# GroupeK.net
KiCad netlist of a schematic drawn in EAGLE
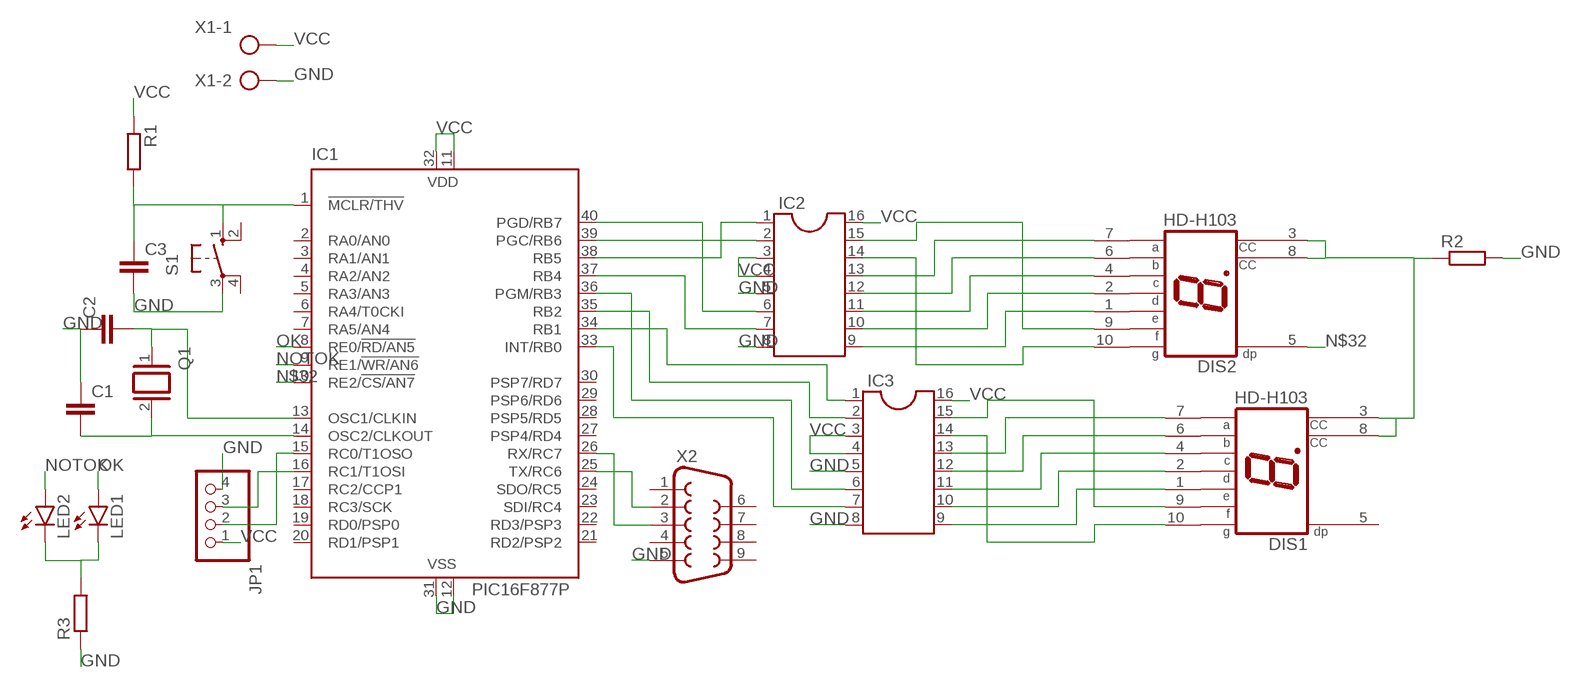
[diagram p0: schematic, sheet 1]

(export (version "E")
  (design (tool "Eeschema 10.0.6"))
  (components
    (comp (ref "C1")
      (value "C-EU025-025X050")
      (footprint "eagle-import:C025-025X050")
      (libsource (lib "eagle-import") (part "C-EU025-025X050"))
    )
    (comp (ref "C2")
      (value "C-EU025-025X050")
      (footprint "eagle-import:C025-025X050")
      (libsource (lib "eagle-import") (part "C-EU025-025X050"))
    )
    (comp (ref "C3")
      (value "C-EU025-025X050")
      (footprint "eagle-import:C025-025X050")
      (libsource (lib "eagle-import") (part "C-EU025-025X050"))
    )
    (comp (ref "DIS1")
      (value "HD-H103")
      (footprint "eagle-import:HDSP-M")
      (libsource (lib "eagle-import") (part "HD-H103"))
    )
    (comp (ref "DIS2")
      (value "HD-H103")
      (footprint "eagle-import:HDSP-M")
      (libsource (lib "eagle-import") (part "HD-H103"))
    )
    (comp (ref "IC1")
      (value "PIC16F877P")
      (footprint "eagle-import:DIL40")
      (fields (field (name "MF") "MICROCHIP") (field (name "MPN") "PIC16F877-04/P"))
      (libsource (lib "eagle-import") (part "PIC16F87P7"))
    )
    (comp (ref "IC2")
      (value "DIL16")
      (footprint "eagle-import:DIL16")
      (libsource (lib "eagle-import") (part "DIL16"))
    )
    (comp (ref "IC3")
      (value "DIL16")
      (footprint "eagle-import:DIL16")
      (libsource (lib "eagle-import") (part "DIL16"))
    )
    (comp (ref "JP1")
      (value "PINHD-1X4")
      (footprint "eagle-import:1X04")
      (libsource (lib "eagle-import") (part "PINHD-1X4"))
    )
    (comp (ref "LED1")
      (value "LED5MM")
      (footprint "eagle-import:LED5MM")
      (libsource (lib "eagle-import") (part "LED5MM"))
    )
    (comp (ref "LED2")
      (value "LED5MM")
      (footprint "eagle-import:LED5MM")
      (libsource (lib "eagle-import") (part "LED5MM"))
    )
    (comp (ref "Q1")
      (value "XTAL/S")
      (footprint "eagle-import:QS")
      (libsource (lib "eagle-import") (part "XTAL/S"))
    )
    (comp (ref "R1")
      (value "R-EU_0207/10")
      (footprint "eagle-import:0207_10")
      (libsource (lib "eagle-import") (part "R-EU_0207/10"))
    )
    (comp (ref "R2")
      (value "R-EU_0207/10")
      (footprint "eagle-import:0207_10")
      (libsource (lib "eagle-import") (part "R-EU_0207/10"))
    )
    (comp (ref "R3")
      (value "R-EU_0207/10")
      (footprint "eagle-import:0207_10")
      (libsource (lib "eagle-import") (part "R-EU_0207/10"))
    )
    (comp (ref "S1")
      (value "10-XX")
      (footprint "eagle-import:B3F-10XX")
      (fields (field (name "MPN") "B3F-1000"))
      (libsource (lib "eagle-import") (part "10-XX"))
    )
    (comp (ref "X1")
      (value "AK300/2")
      (footprint "eagle-import:AK300_2")
      (libsource (lib "eagle-import") (part "AK300/2"))
    )
    (comp (ref "X2")
      (value "F09H")
      (footprint "eagle-import:F09H")
      (libsource (lib "eagle-import") (part "F09H"))
    )
  )
  (nets
    (net (code "1") (name "/GND") (class "Default")
      (node (ref "C1") (pin "1") (pinfunction "1_1") (pintype "passive"))
      (node (ref "C2") (pin "1") (pinfunction "1_1") (pintype "passive"))
      (node (ref "C3") (pin "2") (pinfunction "2_2") (pintype "passive"))
      (node (ref "IC1") (pin "12") (pinfunction "VSS_12") (pintype "power_in"))
      (node (ref "IC1") (pin "31") (pinfunction "VSS_31") (pintype "power_in"))
      (node (ref "IC2") (pin "5") (pinfunction "5_5") (pintype "passive"))
      (node (ref "IC2") (pin "8") (pinfunction "8_8") (pintype "passive"))
      (node (ref "IC3") (pin "5") (pinfunction "5_5") (pintype "passive"))
      (node (ref "IC3") (pin "8") (pinfunction "8_8") (pintype "passive"))
      (node (ref "JP1") (pin "4") (pinfunction "4_4") (pintype "passive"))
      (node (ref "R2") (pin "2") (pinfunction "2_2") (pintype "passive"))
      (node (ref "R3") (pin "1") (pinfunction "1_1") (pintype "passive"))
      (node (ref "S1") (pin "3") (pinfunction "P_3") (pintype "passive"))
      (node (ref "X1") (pin "2") (pinfunction "KL_2") (pintype "passive"))
      (node (ref "X2") (pin "5") (pinfunction "5_5") (pintype "passive"))
    )
    (net (code "2") (name "/N$32") (class "Default")
      (node (ref "DIS2") (pin "5") (pinfunction "DP_5") (pintype "passive"))
      (node (ref "IC1") (pin "10") (pinfunction "RE2/~{CS/AN7}_10") (pintype "bidirectional"))
    )
    (net (code "3") (name "/NOTOK") (class "Default")
      (node (ref "IC1") (pin "9") (pinfunction "RE1/~{WR/AN6}_9") (pintype "bidirectional"))
      (node (ref "LED2") (pin "A") (pinfunction "A_A") (pintype "passive"))
    )
    (net (code "4") (name "/OK") (class "Default")
      (node (ref "IC1") (pin "8") (pinfunction "RE0/~{RD/AN5}_8") (pintype "bidirectional"))
      (node (ref "LED1") (pin "A") (pinfunction "A_A") (pintype "passive"))
    )
    (net (code "5") (name "/VCC") (class "Default")
      (node (ref "IC1") (pin "11") (pinfunction "VDD_11") (pintype "power_in"))
      (node (ref "IC1") (pin "32") (pinfunction "VDD_32") (pintype "power_in"))
      (node (ref "IC2") (pin "16") (pinfunction "16_16") (pintype "passive"))
      (node (ref "IC2") (pin "3") (pinfunction "3_3") (pintype "passive"))
      (node (ref "IC2") (pin "4") (pinfunction "4_4") (pintype "passive"))
      (node (ref "IC3") (pin "16") (pinfunction "16_16") (pintype "passive"))
      (node (ref "IC3") (pin "3") (pinfunction "3_3") (pintype "passive"))
      (node (ref "IC3") (pin "4") (pinfunction "4_4") (pintype "passive"))
      (node (ref "JP1") (pin "1") (pinfunction "1_1") (pintype "passive"))
      (node (ref "R1") (pin "1") (pinfunction "1_1") (pintype "passive"))
      (node (ref "X1") (pin "1") (pinfunction "KL_1") (pintype "passive"))
    )
    (net (code "6") (name "Net-(DIS1-A)") (class "Default")
      (node (ref "DIS1") (pin "7") (pinfunction "A_7") (pintype "passive"))
      (node (ref "IC3") (pin "13") (pinfunction "13_13") (pintype "passive"))
    )
    (net (code "7") (name "Net-(DIS1-B)") (class "Default")
      (node (ref "DIS1") (pin "6") (pinfunction "B_6") (pintype "passive"))
      (node (ref "IC3") (pin "12") (pinfunction "12_12") (pintype "passive"))
    )
    (net (code "8") (name "Net-(DIS1-C)") (class "Default")
      (node (ref "DIS1") (pin "4") (pinfunction "C_4") (pintype "passive"))
      (node (ref "IC3") (pin "11") (pinfunction "11_11") (pintype "passive"))
    )
    (net (code "9") (name "Net-(DIS1-CC-Pad3)") (class "Default")
      (node (ref "DIS1") (pin "3") (pinfunction "CC_3") (pintype "passive"))
      (node (ref "DIS1") (pin "8") (pinfunction "CC_8") (pintype "passive"))
      (node (ref "DIS2") (pin "3") (pinfunction "CC_3") (pintype "passive"))
      (node (ref "DIS2") (pin "8") (pinfunction "CC_8") (pintype "passive"))
      (node (ref "R2") (pin "1") (pinfunction "1_1") (pintype "passive"))
    )
    (net (code "10") (name "Net-(DIS1-D)") (class "Default")
      (node (ref "DIS1") (pin "2") (pinfunction "D_2") (pintype "passive"))
      (node (ref "IC3") (pin "10") (pinfunction "10_10") (pintype "passive"))
    )
    (net (code "11") (name "Net-(DIS1-E)") (class "Default")
      (node (ref "DIS1") (pin "1") (pinfunction "E_1") (pintype "passive"))
      (node (ref "IC3") (pin "9") (pinfunction "9_9") (pintype "passive"))
    )
    (net (code "12") (name "Net-(DIS1-F)") (class "Default")
      (node (ref "DIS1") (pin "9") (pinfunction "F_9") (pintype "passive"))
      (node (ref "IC3") (pin "15") (pinfunction "15_15") (pintype "passive"))
    )
    (net (code "13") (name "Net-(DIS1-G)") (class "Default")
      (node (ref "DIS1") (pin "10") (pinfunction "G_10") (pintype "passive"))
      (node (ref "IC3") (pin "14") (pinfunction "14_14") (pintype "passive"))
    )
    (net (code "14") (name "Net-(DIS2-A)") (class "Default")
      (node (ref "DIS2") (pin "7") (pinfunction "A_7") (pintype "passive"))
      (node (ref "IC2") (pin "13") (pinfunction "13_13") (pintype "passive"))
    )
    (net (code "15") (name "Net-(DIS2-B)") (class "Default")
      (node (ref "DIS2") (pin "6") (pinfunction "B_6") (pintype "passive"))
      (node (ref "IC2") (pin "12") (pinfunction "12_12") (pintype "passive"))
    )
    (net (code "16") (name "Net-(DIS2-C)") (class "Default")
      (node (ref "DIS2") (pin "4") (pinfunction "C_4") (pintype "passive"))
      (node (ref "IC2") (pin "11") (pinfunction "11_11") (pintype "passive"))
    )
    (net (code "17") (name "Net-(DIS2-D)") (class "Default")
      (node (ref "DIS2") (pin "2") (pinfunction "D_2") (pintype "passive"))
      (node (ref "IC2") (pin "10") (pinfunction "10_10") (pintype "passive"))
    )
    (net (code "18") (name "Net-(DIS2-E)") (class "Default")
      (node (ref "DIS2") (pin "1") (pinfunction "E_1") (pintype "passive"))
      (node (ref "IC2") (pin "9") (pinfunction "9_9") (pintype "passive"))
    )
    (net (code "19") (name "Net-(DIS2-F)") (class "Default")
      (node (ref "DIS2") (pin "9") (pinfunction "F_9") (pintype "passive"))
      (node (ref "IC2") (pin "15") (pinfunction "15_15") (pintype "passive"))
    )
    (net (code "20") (name "Net-(DIS2-G)") (class "Default")
      (node (ref "DIS2") (pin "10") (pinfunction "G_10") (pintype "passive"))
      (node (ref "IC2") (pin "14") (pinfunction "14_14") (pintype "passive"))
    )
    (net (code "21") (name "Net-(IC1-INT{slash}RB0)") (class "Default")
      (node (ref "IC1") (pin "33") (pinfunction "INT/RB0_33") (pintype "bidirectional"))
      (node (ref "IC3") (pin "7") (pinfunction "7_7") (pintype "passive"))
    )
    (net (code "22") (name "Net-(IC1-OSC1{slash}CLKIN)") (class "Default")
      (node (ref "C2") (pin "2") (pinfunction "2_2") (pintype "passive"))
      (node (ref "IC1") (pin "13") (pinfunction "OSC1/CLKIN_13") (pintype "input"))
      (node (ref "Q1") (pin "1") (pinfunction "1_1") (pintype "passive"))
    )
    (net (code "23") (name "Net-(IC1-OSC2{slash}CLKOUT)") (class "Default")
      (node (ref "C1") (pin "2") (pinfunction "2_2") (pintype "passive"))
      (node (ref "IC1") (pin "14") (pinfunction "OSC2/CLKOUT_14") (pintype "output"))
      (node (ref "Q1") (pin "2") (pinfunction "2_2") (pintype "passive"))
    )
    (net (code "24") (name "Net-(IC1-PGC{slash}RB6)") (class "Default")
      (node (ref "IC1") (pin "39") (pinfunction "PGC/RB6_39") (pintype "bidirectional"))
      (node (ref "IC2") (pin "2") (pinfunction "2_2") (pintype "passive"))
    )
    (net (code "25") (name "Net-(IC1-PGD{slash}RB7)") (class "Default")
      (node (ref "IC1") (pin "40") (pinfunction "PGD/RB7_40") (pintype "bidirectional"))
      (node (ref "IC2") (pin "6") (pinfunction "6_6") (pintype "passive"))
    )
    (net (code "26") (name "Net-(IC1-PGM{slash}RB3)") (class "Default")
      (node (ref "IC1") (pin "36") (pinfunction "PGM/RB3_36") (pintype "bidirectional"))
      (node (ref "IC3") (pin "6") (pinfunction "6_6") (pintype "passive"))
    )
    (net (code "27") (name "Net-(IC1-RB1)") (class "Default")
      (node (ref "IC1") (pin "34") (pinfunction "RB1_34") (pintype "bidirectional"))
      (node (ref "IC3") (pin "1") (pinfunction "1_1") (pintype "passive"))
    )
    (net (code "28") (name "Net-(IC1-RB2)") (class "Default")
      (node (ref "IC1") (pin "35") (pinfunction "RB2_35") (pintype "bidirectional"))
      (node (ref "IC3") (pin "2") (pinfunction "2_2") (pintype "passive"))
    )
    (net (code "29") (name "Net-(IC1-RB4)") (class "Default")
      (node (ref "IC1") (pin "37") (pinfunction "RB4_37") (pintype "bidirectional"))
      (node (ref "IC2") (pin "7") (pinfunction "7_7") (pintype "passive"))
    )
    (net (code "30") (name "Net-(IC1-RB5)") (class "Default")
      (node (ref "IC1") (pin "38") (pinfunction "RB5_38") (pintype "bidirectional"))
      (node (ref "IC2") (pin "1") (pinfunction "1_1") (pintype "passive"))
    )
    (net (code "31") (name "Net-(IC1-RC0{slash}T1OSO)") (class "Default")
      (node (ref "IC1") (pin "15") (pinfunction "RC0/T1OSO_15") (pintype "bidirectional"))
      (node (ref "JP1") (pin "2") (pinfunction "2_2") (pintype "passive"))
    )
    (net (code "32") (name "Net-(IC1-RC1{slash}T1OSI)") (class "Default")
      (node (ref "IC1") (pin "16") (pinfunction "RC1/T1OSI_16") (pintype "bidirectional"))
      (node (ref "JP1") (pin "3") (pinfunction "3_3") (pintype "passive"))
    )
    (net (code "33") (name "Net-(IC1-RX{slash}RC7)") (class "Default")
      (node (ref "IC1") (pin "26") (pinfunction "RX/RC7_26") (pintype "bidirectional"))
      (node (ref "X2") (pin "3") (pinfunction "3_3") (pintype "passive"))
    )
    (net (code "34") (name "Net-(IC1-TX{slash}RC6)") (class "Default")
      (node (ref "IC1") (pin "25") (pinfunction "TX/RC6_25") (pintype "bidirectional"))
      (node (ref "X2") (pin "2") (pinfunction "2_2") (pintype "passive"))
    )
    (net (code "35") (name "Net-(IC1-~{MCLR{slash}THV})") (class "Default")
      (node (ref "C3") (pin "1") (pinfunction "1_1") (pintype "passive"))
      (node (ref "IC1") (pin "1") (pinfunction "~{MCLR/THV}_1") (pintype "input"))
      (node (ref "R1") (pin "2") (pinfunction "2_2") (pintype "passive"))
      (node (ref "S1") (pin "1") (pinfunction "S_1") (pintype "passive"))
    )
    (net (code "36") (name "Net-(LED1-C)") (class "Default")
      (node (ref "LED1") (pin "K") (pinfunction "C_K") (pintype "passive"))
      (node (ref "LED2") (pin "K") (pinfunction "C_K") (pintype "passive"))
      (node (ref "R3") (pin "2") (pinfunction "2_2") (pintype "passive"))
    )
    (net (code "37") (name "unconnected-(DIS1-DP-Pad5)") (class "Default")
      (node (ref "DIS1") (pin "5") (pinfunction "DP_5") (pintype "passive"))
    )
    (net (code "38") (name "unconnected-(IC1-PSP4{slash}RD4-Pad27)") (class "Default")
      (node (ref "IC1") (pin "27") (pinfunction "PSP4/RD4_27") (pintype "bidirectional"))
    )
    (net (code "39") (name "unconnected-(IC1-PSP5{slash}RD5-Pad28)") (class "Default")
      (node (ref "IC1") (pin "28") (pinfunction "PSP5/RD5_28") (pintype "bidirectional"))
    )
    (net (code "40") (name "unconnected-(IC1-PSP6{slash}RD6-Pad29)") (class "Default")
      (node (ref "IC1") (pin "29") (pinfunction "PSP6/RD6_29") (pintype "bidirectional"))
    )
    (net (code "41") (name "unconnected-(IC1-PSP7{slash}RD7-Pad30)") (class "Default")
      (node (ref "IC1") (pin "30") (pinfunction "PSP7/RD7_30") (pintype "bidirectional"))
    )
    (net (code "42") (name "unconnected-(IC1-RA0{slash}AN0-Pad2)") (class "Default")
      (node (ref "IC1") (pin "2") (pinfunction "RA0/AN0_2") (pintype "bidirectional"))
    )
    (net (code "43") (name "unconnected-(IC1-RA1{slash}AN1-Pad3)") (class "Default")
      (node (ref "IC1") (pin "3") (pinfunction "RA1/AN1_3") (pintype "bidirectional"))
    )
    (net (code "44") (name "unconnected-(IC1-RA2{slash}AN2-Pad4)") (class "Default")
      (node (ref "IC1") (pin "4") (pinfunction "RA2/AN2_4") (pintype "bidirectional"))
    )
    (net (code "45") (name "unconnected-(IC1-RA3{slash}AN3-Pad5)") (class "Default")
      (node (ref "IC1") (pin "5") (pinfunction "RA3/AN3_5") (pintype "bidirectional"))
    )
    (net (code "46") (name "unconnected-(IC1-RA4{slash}T0CKI-Pad6)") (class "Default")
      (node (ref "IC1") (pin "6") (pinfunction "RA4/T0CKI_6") (pintype "bidirectional"))
    )
    (net (code "47") (name "unconnected-(IC1-RA5{slash}AN4-Pad7)") (class "Default")
      (node (ref "IC1") (pin "7") (pinfunction "RA5/AN4_7") (pintype "bidirectional"))
    )
    (net (code "48") (name "unconnected-(IC1-RC2{slash}CCP1-Pad17)") (class "Default")
      (node (ref "IC1") (pin "17") (pinfunction "RC2/CCP1_17") (pintype "bidirectional"))
    )
    (net (code "49") (name "unconnected-(IC1-RC3{slash}SCK-Pad18)") (class "Default")
      (node (ref "IC1") (pin "18") (pinfunction "RC3/SCK_18") (pintype "bidirectional"))
    )
    (net (code "50") (name "unconnected-(IC1-RD0{slash}PSP0-Pad19)") (class "Default")
      (node (ref "IC1") (pin "19") (pinfunction "RD0/PSP0_19") (pintype "bidirectional"))
    )
    (net (code "51") (name "unconnected-(IC1-RD1{slash}PSP1-Pad20)") (class "Default")
      (node (ref "IC1") (pin "20") (pinfunction "RD1/PSP1_20") (pintype "bidirectional"))
    )
    (net (code "52") (name "unconnected-(IC1-RD2{slash}PSP2-Pad21)") (class "Default")
      (node (ref "IC1") (pin "21") (pinfunction "RD2/PSP2_21") (pintype "bidirectional"))
    )
    (net (code "53") (name "unconnected-(IC1-RD3{slash}PSP3-Pad22)") (class "Default")
      (node (ref "IC1") (pin "22") (pinfunction "RD3/PSP3_22") (pintype "bidirectional"))
    )
    (net (code "54") (name "unconnected-(IC1-SDI{slash}RC4-Pad23)") (class "Default")
      (node (ref "IC1") (pin "23") (pinfunction "SDI/RC4_23") (pintype "bidirectional"))
    )
    (net (code "55") (name "unconnected-(IC1-SDO{slash}RC5-Pad24)") (class "Default")
      (node (ref "IC1") (pin "24") (pinfunction "SDO/RC5_24") (pintype "bidirectional"))
    )
    (net (code "56") (name "unconnected-(S1-P1-Pad4)") (class "Default")
      (node (ref "S1") (pin "4") (pinfunction "P1_4") (pintype "passive"))
    )
    (net (code "57") (name "unconnected-(S1-S1-Pad2)") (class "Default")
      (node (ref "S1") (pin "2") (pinfunction "S1_2") (pintype "passive"))
    )
    (net (code "58") (name "unconnected-(X2-Pad1)") (class "Default")
      (node (ref "X2") (pin "1") (pinfunction "1_1") (pintype "passive"))
    )
    (net (code "59") (name "unconnected-(X2-Pad4)") (class "Default")
      (node (ref "X2") (pin "4") (pinfunction "4_4") (pintype "passive"))
    )
    (net (code "60") (name "unconnected-(X2-Pad6)") (class "Default")
      (node (ref "X2") (pin "6") (pinfunction "6_6") (pintype "passive"))
    )
    (net (code "61") (name "unconnected-(X2-Pad7)") (class "Default")
      (node (ref "X2") (pin "7") (pinfunction "7_7") (pintype "passive"))
    )
    (net (code "62") (name "unconnected-(X2-Pad8)") (class "Default")
      (node (ref "X2") (pin "8") (pinfunction "8_8") (pintype "passive"))
    )
    (net (code "63") (name "unconnected-(X2-Pad9)") (class "Default")
      (node (ref "X2") (pin "9") (pinfunction "9_9") (pintype "passive"))
    )
  )
)
